# 08_BALUN.net
KiCad netlist of a schematic drawn in Altium Designer
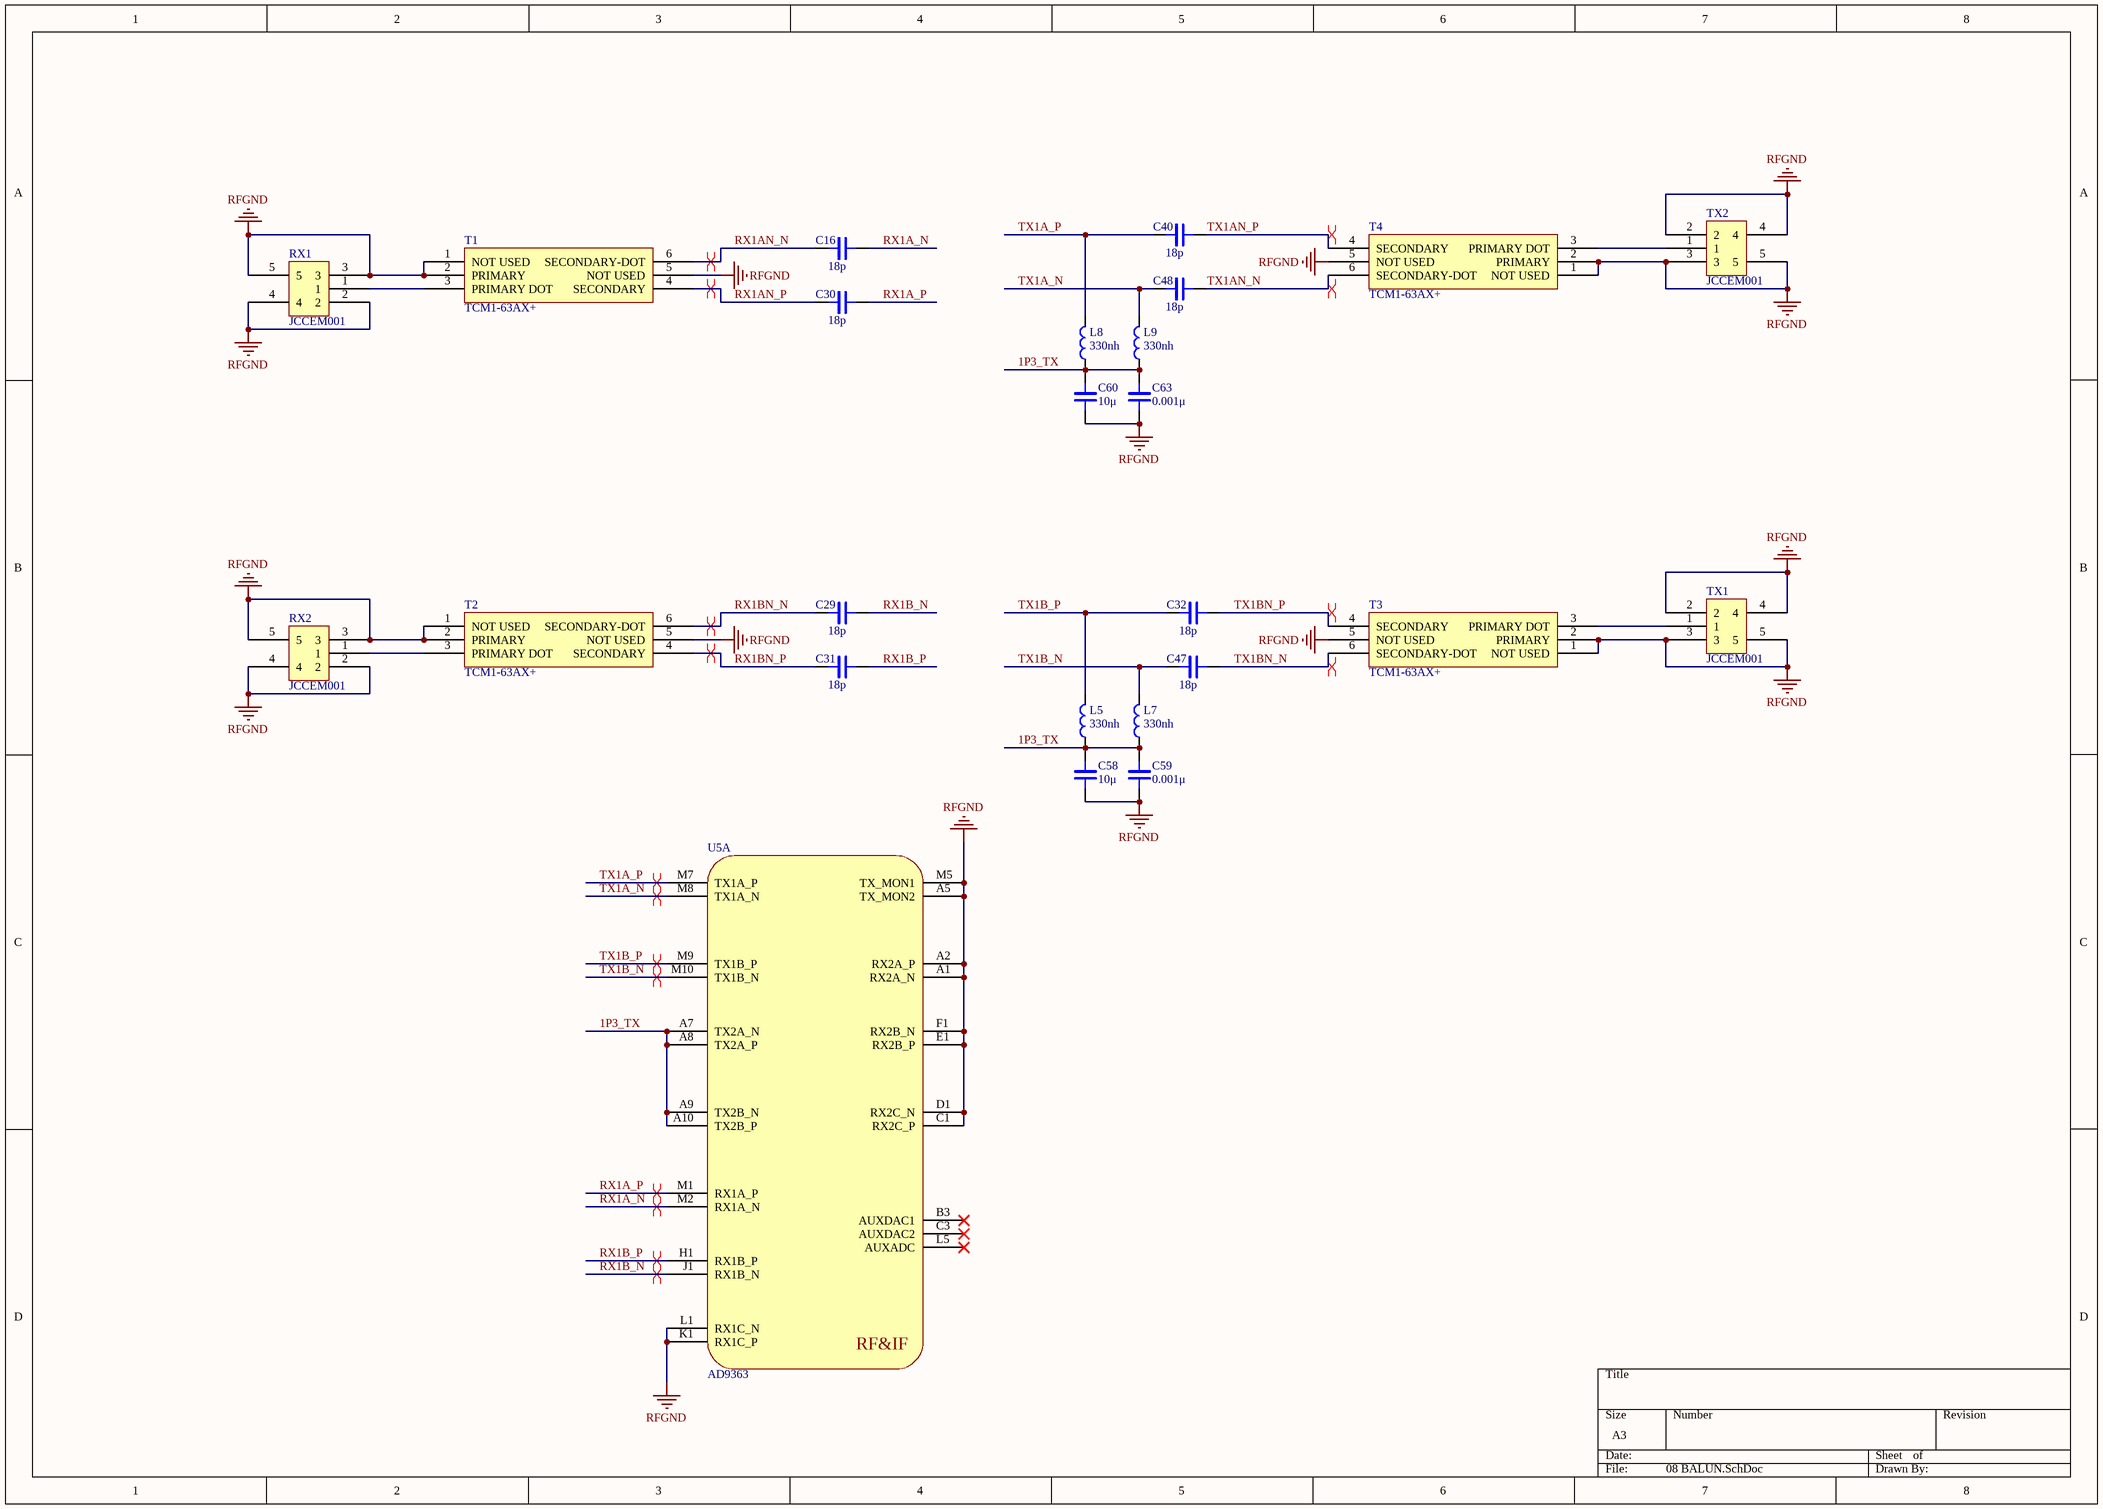
[diagram p0: 08 BALUN.SchDoc]

(export (version "E")
  (design (tool "Eeschema 10.0.6"))
  (components
    (comp (ref "C16")
      (value "18p")
      (footprint "LC-0402_C")
      (description "Capacitor")
      (libsource (lib "DDR3_xc7z010-clg400") (part "CAP_1"))
    )
    (comp (ref "C29")
      (value "18p")
      (footprint "LC-0402_C")
      (description "Capacitor")
      (libsource (lib "DDR3_xc7z010-clg400") (part "CAP_1"))
    )
    (comp (ref "C30")
      (value "18p")
      (footprint "LC-0402_C")
      (description "Capacitor")
      (libsource (lib "DDR3_xc7z010-clg400") (part "CAP_1"))
    )
    (comp (ref "C31")
      (value "18p")
      (footprint "LC-0402_C")
      (description "Capacitor")
      (libsource (lib "DDR3_xc7z010-clg400") (part "CAP_1"))
    )
    (comp (ref "C32")
      (value "18p")
      (footprint "LC-0402_C")
      (description "Capacitor")
      (libsource (lib "DDR3_xc7z010-clg400") (part "CAP_1"))
    )
    (comp (ref "C40")
      (value "18p")
      (footprint "LC-0402_C")
      (description "Capacitor")
      (libsource (lib "DDR3_xc7z010-clg400") (part "CAP_1"))
    )
    (comp (ref "C47")
      (value "18p")
      (footprint "LC-0402_C")
      (description "Capacitor")
      (libsource (lib "DDR3_xc7z010-clg400") (part "CAP_1"))
    )
    (comp (ref "C48")
      (value "18p")
      (footprint "LC-0402_C")
      (description "Capacitor")
      (libsource (lib "DDR3_xc7z010-clg400") (part "CAP_1"))
    )
    (comp (ref "C58")
      (value "10μ")
      (footprint "LC-0402_C")
      (description "Capacitor")
      (libsource (lib "DDR3_xc7z010-clg400") (part "CAP_2"))
    )
    (comp (ref "C59")
      (value "0.001μ")
      (footprint "LC-0402_C")
      (description "Capacitor")
      (libsource (lib "DDR3_xc7z010-clg400") (part "CAP_2"))
    )
    (comp (ref "C60")
      (value "10μ")
      (footprint "LC-0402_C")
      (description "Capacitor")
      (libsource (lib "DDR3_xc7z010-clg400") (part "CAP_2"))
    )
    (comp (ref "C63")
      (value "0.001μ")
      (footprint "LC-0402_C")
      (description "Capacitor")
      (libsource (lib "DDR3_xc7z010-clg400") (part "CAP_2"))
    )
    (comp (ref "L5")
      (value "330nh")
      (footprint "LC-0603_L")
      (description "Inductance")
      (libsource (lib "DDR3_xc7z010-clg400") (part "INDUCTANCE"))
    )
    (comp (ref "L7")
      (value "330nh")
      (footprint "LC-0603_L")
      (description "Inductance")
      (libsource (lib "DDR3_xc7z010-clg400") (part "INDUCTANCE"))
    )
    (comp (ref "L8")
      (value "330nh")
      (footprint "LC-0603_L")
      (description "Inductance")
      (libsource (lib "DDR3_xc7z010-clg400") (part "INDUCTANCE"))
    )
    (comp (ref "L9")
      (value "330nh")
      (footprint "LC-0603_L")
      (description "Inductance")
      (libsource (lib "DDR3_xc7z010-clg400") (part "INDUCTANCE"))
    )
    (comp (ref "RX1")
      (value "JCCEM001")
      (footprint "CNSMARAL687W375H171")
      (libsource (lib "Schlib1") (part "JCCEM001"))
    )
    (comp (ref "RX2")
      (value "JCCEM001")
      (footprint "CNSMARAL687W375H171")
      (libsource (lib "Schlib1") (part "JCCEM001"))
    )
    (comp (ref "T1")
      (value "TCM1-63AX+")
      (footprint "TSML150W160H160")
      (libsource (lib "Schlib1") (part "TCM1-63AX+"))
    )
    (comp (ref "T2")
      (value "TCM1-63AX+")
      (footprint "TSML150W160H160")
      (libsource (lib "Schlib1") (part "TCM1-63AX+"))
    )
    (comp (ref "T3")
      (value "TCM1-63AX+")
      (footprint "TSML150W160H160")
      (libsource (lib "") (part "TCM1-63AX+_1"))
    )
    (comp (ref "T4")
      (value "TCM1-63AX+")
      (footprint "TSML150W160H160")
      (libsource (lib "") (part "TCM1-63AX+_1"))
    )
    (comp (ref "TX1")
      (value "JCCEM001")
      (footprint "CNSMARAL687W375H171")
      (libsource (lib "") (part "JCCEM001_1"))
    )
    (comp (ref "TX2")
      (value "JCCEM001")
      (footprint "CNSMARAL687W375H171")
      (libsource (lib "") (part "JCCEM001_1"))
    )
    (comp (ref "U5") (value "AD9363") (footprint "AD936X") (libsource (lib "Schlib1") (part "AD9363")))
  )
  (nets
    (net (code "1") (name "/1P3_TX") (class "Default")
      (node (ref "C58") (pin "1") (pinfunction "1_1") (pintype "passive"))
      (node (ref "C59") (pin "2") (pinfunction "2_2") (pintype "passive"))
      (node (ref "C60") (pin "1") (pinfunction "1_1") (pintype "passive"))
      (node (ref "C63") (pin "2") (pinfunction "2_2") (pintype "passive"))
      (node (ref "L5") (pin "1") (pinfunction "1_1") (pintype "passive"))
      (node (ref "L7") (pin "1") (pinfunction "1_1") (pintype "passive"))
      (node (ref "L8") (pin "1") (pinfunction "1_1") (pintype "passive"))
      (node (ref "L9") (pin "1") (pinfunction "1_1") (pintype "passive"))
      (node (ref "U5") (pin "A10") (pinfunction "TX2B_P_A10") (pintype "passive"))
      (node (ref "U5") (pin "A7") (pinfunction "TX2A_N_A7") (pintype "passive"))
      (node (ref "U5") (pin "A8") (pinfunction "TX2A_P_A8") (pintype "passive"))
      (node (ref "U5") (pin "A9") (pinfunction "TX2B_N_A9") (pintype "passive"))
    )
    (net (code "2") (name "/RX1AN_N") (class "Default")
      (node (ref "C16") (pin "1") (pinfunction "1_1") (pintype "passive"))
      (node (ref "T1") (pin "6") (pinfunction "SECONDARY-DOT_6") (pintype "passive"))
    )
    (net (code "3") (name "/RX1AN_P") (class "Default")
      (node (ref "C30") (pin "1") (pinfunction "1_1") (pintype "passive"))
      (node (ref "T1") (pin "4") (pinfunction "SECONDARY_4") (pintype "passive"))
    )
    (net (code "4") (name "/RX1A_N") (class "Default")
      (node (ref "C16") (pin "2") (pinfunction "2_2") (pintype "passive"))
      (node (ref "U5") (pin "M2") (pinfunction "RX1A_N_M2") (pintype "passive"))
    )
    (net (code "5") (name "/RX1A_P") (class "Default")
      (node (ref "C30") (pin "2") (pinfunction "2_2") (pintype "passive"))
      (node (ref "U5") (pin "M1") (pinfunction "RX1A_P_M1") (pintype "passive"))
    )
    (net (code "6") (name "/RX1BN_N") (class "Default")
      (node (ref "C29") (pin "1") (pinfunction "1_1") (pintype "passive"))
      (node (ref "T2") (pin "6") (pinfunction "SECONDARY-DOT_6") (pintype "passive"))
    )
    (net (code "7") (name "/RX1BN_P") (class "Default")
      (node (ref "C31") (pin "1") (pinfunction "1_1") (pintype "passive"))
      (node (ref "T2") (pin "4") (pinfunction "SECONDARY_4") (pintype "passive"))
    )
    (net (code "8") (name "/RX1B_N") (class "Default")
      (node (ref "C29") (pin "2") (pinfunction "2_2") (pintype "passive"))
      (node (ref "U5") (pin "J1") (pinfunction "RX1B_N_J1") (pintype "passive"))
    )
    (net (code "9") (name "/RX1B_P") (class "Default")
      (node (ref "C31") (pin "2") (pinfunction "2_2") (pintype "passive"))
      (node (ref "U5") (pin "H1") (pinfunction "RX1B_P_H1") (pintype "passive"))
    )
    (net (code "10") (name "/TX1AN_N") (class "Default")
      (node (ref "C48") (pin "2") (pinfunction "2_2") (pintype "passive"))
      (node (ref "T4") (pin "6") (pinfunction "SECONDARY-DOT_6") (pintype "passive"))
    )
    (net (code "11") (name "/TX1AN_P") (class "Default")
      (node (ref "C40") (pin "2") (pinfunction "2_2") (pintype "passive"))
      (node (ref "T4") (pin "4") (pinfunction "SECONDARY_4") (pintype "passive"))
    )
    (net (code "12") (name "/TX1A_N") (class "Default")
      (node (ref "C48") (pin "1") (pinfunction "1_1") (pintype "passive"))
      (node (ref "L9") (pin "2") (pinfunction "2_2") (pintype "passive"))
      (node (ref "U5") (pin "M8") (pinfunction "TX1A_N_M8") (pintype "passive"))
    )
    (net (code "13") (name "/TX1A_P") (class "Default")
      (node (ref "C40") (pin "1") (pinfunction "1_1") (pintype "passive"))
      (node (ref "L8") (pin "2") (pinfunction "2_2") (pintype "passive"))
      (node (ref "U5") (pin "M7") (pinfunction "TX1A_P_M7") (pintype "passive"))
    )
    (net (code "14") (name "/TX1BN_N") (class "Default")
      (node (ref "C47") (pin "2") (pinfunction "2_2") (pintype "passive"))
      (node (ref "T3") (pin "6") (pinfunction "SECONDARY-DOT_6") (pintype "passive"))
    )
    (net (code "15") (name "/TX1BN_P") (class "Default")
      (node (ref "C32") (pin "2") (pinfunction "2_2") (pintype "passive"))
      (node (ref "T3") (pin "4") (pinfunction "SECONDARY_4") (pintype "passive"))
    )
    (net (code "16") (name "/TX1B_N") (class "Default")
      (node (ref "C47") (pin "1") (pinfunction "1_1") (pintype "passive"))
      (node (ref "L7") (pin "2") (pinfunction "2_2") (pintype "passive"))
      (node (ref "U5") (pin "M10") (pinfunction "TX1B_N_M10") (pintype "passive"))
    )
    (net (code "17") (name "/TX1B_P") (class "Default")
      (node (ref "C32") (pin "1") (pinfunction "1_1") (pintype "passive"))
      (node (ref "L5") (pin "2") (pinfunction "2_2") (pintype "passive"))
      (node (ref "U5") (pin "M9") (pinfunction "TX1B_P_M9") (pintype "passive"))
    )
    (net (code "18") (name "Net-(T1-PRIMARY_DOT)") (class "Default")
      (node (ref "RX1") (pin "1") (pinfunction "1_1") (pintype "passive"))
      (node (ref "T1") (pin "3") (pinfunction "PRIMARY_DOT_3") (pintype "passive"))
    )
    (net (code "19") (name "Net-(T2-PRIMARY_DOT)") (class "Default")
      (node (ref "RX2") (pin "1") (pinfunction "1_1") (pintype "passive"))
      (node (ref "T2") (pin "3") (pinfunction "PRIMARY_DOT_3") (pintype "passive"))
    )
    (net (code "20") (name "Net-(T3-PRIMARY_DOT)") (class "Default")
      (node (ref "T3") (pin "3") (pinfunction "PRIMARY_DOT_3") (pintype "passive"))
      (node (ref "TX1") (pin "1") (pinfunction "1_1") (pintype "passive"))
    )
    (net (code "21") (name "Net-(T4-PRIMARY_DOT)") (class "Default")
      (node (ref "T4") (pin "3") (pinfunction "PRIMARY_DOT_3") (pintype "passive"))
      (node (ref "TX2") (pin "1") (pinfunction "1_1") (pintype "passive"))
    )
    (net (code "22") (name "RFGND") (class "Default")
      (node (ref "C58") (pin "2") (pinfunction "2_2") (pintype "passive"))
      (node (ref "C59") (pin "1") (pinfunction "1_1") (pintype "passive"))
      (node (ref "C60") (pin "2") (pinfunction "2_2") (pintype "passive"))
      (node (ref "C63") (pin "1") (pinfunction "1_1") (pintype "passive"))
      (node (ref "RX1") (pin "2") (pinfunction "2_2") (pintype "passive"))
      (node (ref "RX1") (pin "3") (pinfunction "3_3") (pintype "passive"))
      (node (ref "RX1") (pin "4") (pinfunction "4_4") (pintype "passive"))
      (node (ref "RX1") (pin "5") (pinfunction "5_5") (pintype "passive"))
      (node (ref "RX2") (pin "2") (pinfunction "2_2") (pintype "passive"))
      (node (ref "RX2") (pin "3") (pinfunction "3_3") (pintype "passive"))
      (node (ref "RX2") (pin "4") (pinfunction "4_4") (pintype "passive"))
      (node (ref "RX2") (pin "5") (pinfunction "5_5") (pintype "passive"))
      (node (ref "T1") (pin "1") (pinfunction "NOT_USED_1") (pintype "passive"))
      (node (ref "T1") (pin "2") (pinfunction "PRIMARY_2") (pintype "passive"))
      (node (ref "T1") (pin "5") (pinfunction "NOT_USED_5") (pintype "passive"))
      (node (ref "T2") (pin "1") (pinfunction "NOT_USED_1") (pintype "passive"))
      (node (ref "T2") (pin "2") (pinfunction "PRIMARY_2") (pintype "passive"))
      (node (ref "T2") (pin "5") (pinfunction "NOT_USED_5") (pintype "passive"))
      (node (ref "T3") (pin "1") (pinfunction "NOT_USED_1") (pintype "passive"))
      (node (ref "T3") (pin "2") (pinfunction "PRIMARY_2") (pintype "passive"))
      (node (ref "T3") (pin "5") (pinfunction "NOT_USED_5") (pintype "passive"))
      (node (ref "T4") (pin "1") (pinfunction "NOT_USED_1") (pintype "passive"))
      (node (ref "T4") (pin "2") (pinfunction "PRIMARY_2") (pintype "passive"))
      (node (ref "T4") (pin "5") (pinfunction "NOT_USED_5") (pintype "passive"))
      (node (ref "TX1") (pin "2") (pinfunction "2_2") (pintype "passive"))
      (node (ref "TX1") (pin "3") (pinfunction "3_3") (pintype "passive"))
      (node (ref "TX1") (pin "4") (pinfunction "4_4") (pintype "passive"))
      (node (ref "TX1") (pin "5") (pinfunction "5_5") (pintype "passive"))
      (node (ref "TX2") (pin "2") (pinfunction "2_2") (pintype "passive"))
      (node (ref "TX2") (pin "3") (pinfunction "3_3") (pintype "passive"))
      (node (ref "TX2") (pin "4") (pinfunction "4_4") (pintype "passive"))
      (node (ref "TX2") (pin "5") (pinfunction "5_5") (pintype "passive"))
      (node (ref "U5") (pin "A1") (pinfunction "RX2A_N_A1") (pintype "passive"))
      (node (ref "U5") (pin "A2") (pinfunction "RX2A_P_A2") (pintype "passive"))
      (node (ref "U5") (pin "A5") (pinfunction "TX_MON2_A5") (pintype "passive"))
      (node (ref "U5") (pin "C1") (pinfunction "RX2C_P_C1") (pintype "passive"))
      (node (ref "U5") (pin "D1") (pinfunction "RX2C_N_D1") (pintype "passive"))
      (node (ref "U5") (pin "E1") (pinfunction "RX2B_P_E1") (pintype "passive"))
      (node (ref "U5") (pin "F1") (pinfunction "RX2B_N_F1") (pintype "passive"))
      (node (ref "U5") (pin "K1") (pinfunction "RX1C_P_K1") (pintype "passive"))
      (node (ref "U5") (pin "L1") (pinfunction "RX1C_N_L1") (pintype "passive"))
      (node (ref "U5") (pin "M5") (pinfunction "TX_MON1_M5") (pintype "passive"))
    )
    (net (code "23") (name "unconnected-(U5A-AUXADC-PadL5)") (class "Default")
      (node (ref "U5") (pin "L5") (pinfunction "AUXADC_L5") (pintype "passive+no_connect"))
    )
    (net (code "24") (name "unconnected-(U5A-AUXDAC1-PadB3)") (class "Default")
      (node (ref "U5") (pin "B3") (pinfunction "AUXDAC1_B3") (pintype "passive+no_connect"))
    )
    (net (code "25") (name "unconnected-(U5A-AUXDAC2-PadC3)") (class "Default")
      (node (ref "U5") (pin "C3") (pinfunction "AUXDAC2_C3") (pintype "passive+no_connect"))
    )
  )
)
